# SCH_NFC-Card-Brianna_2024-10-25.net
KiCad netlist of a schematic drawn in EasyEDA
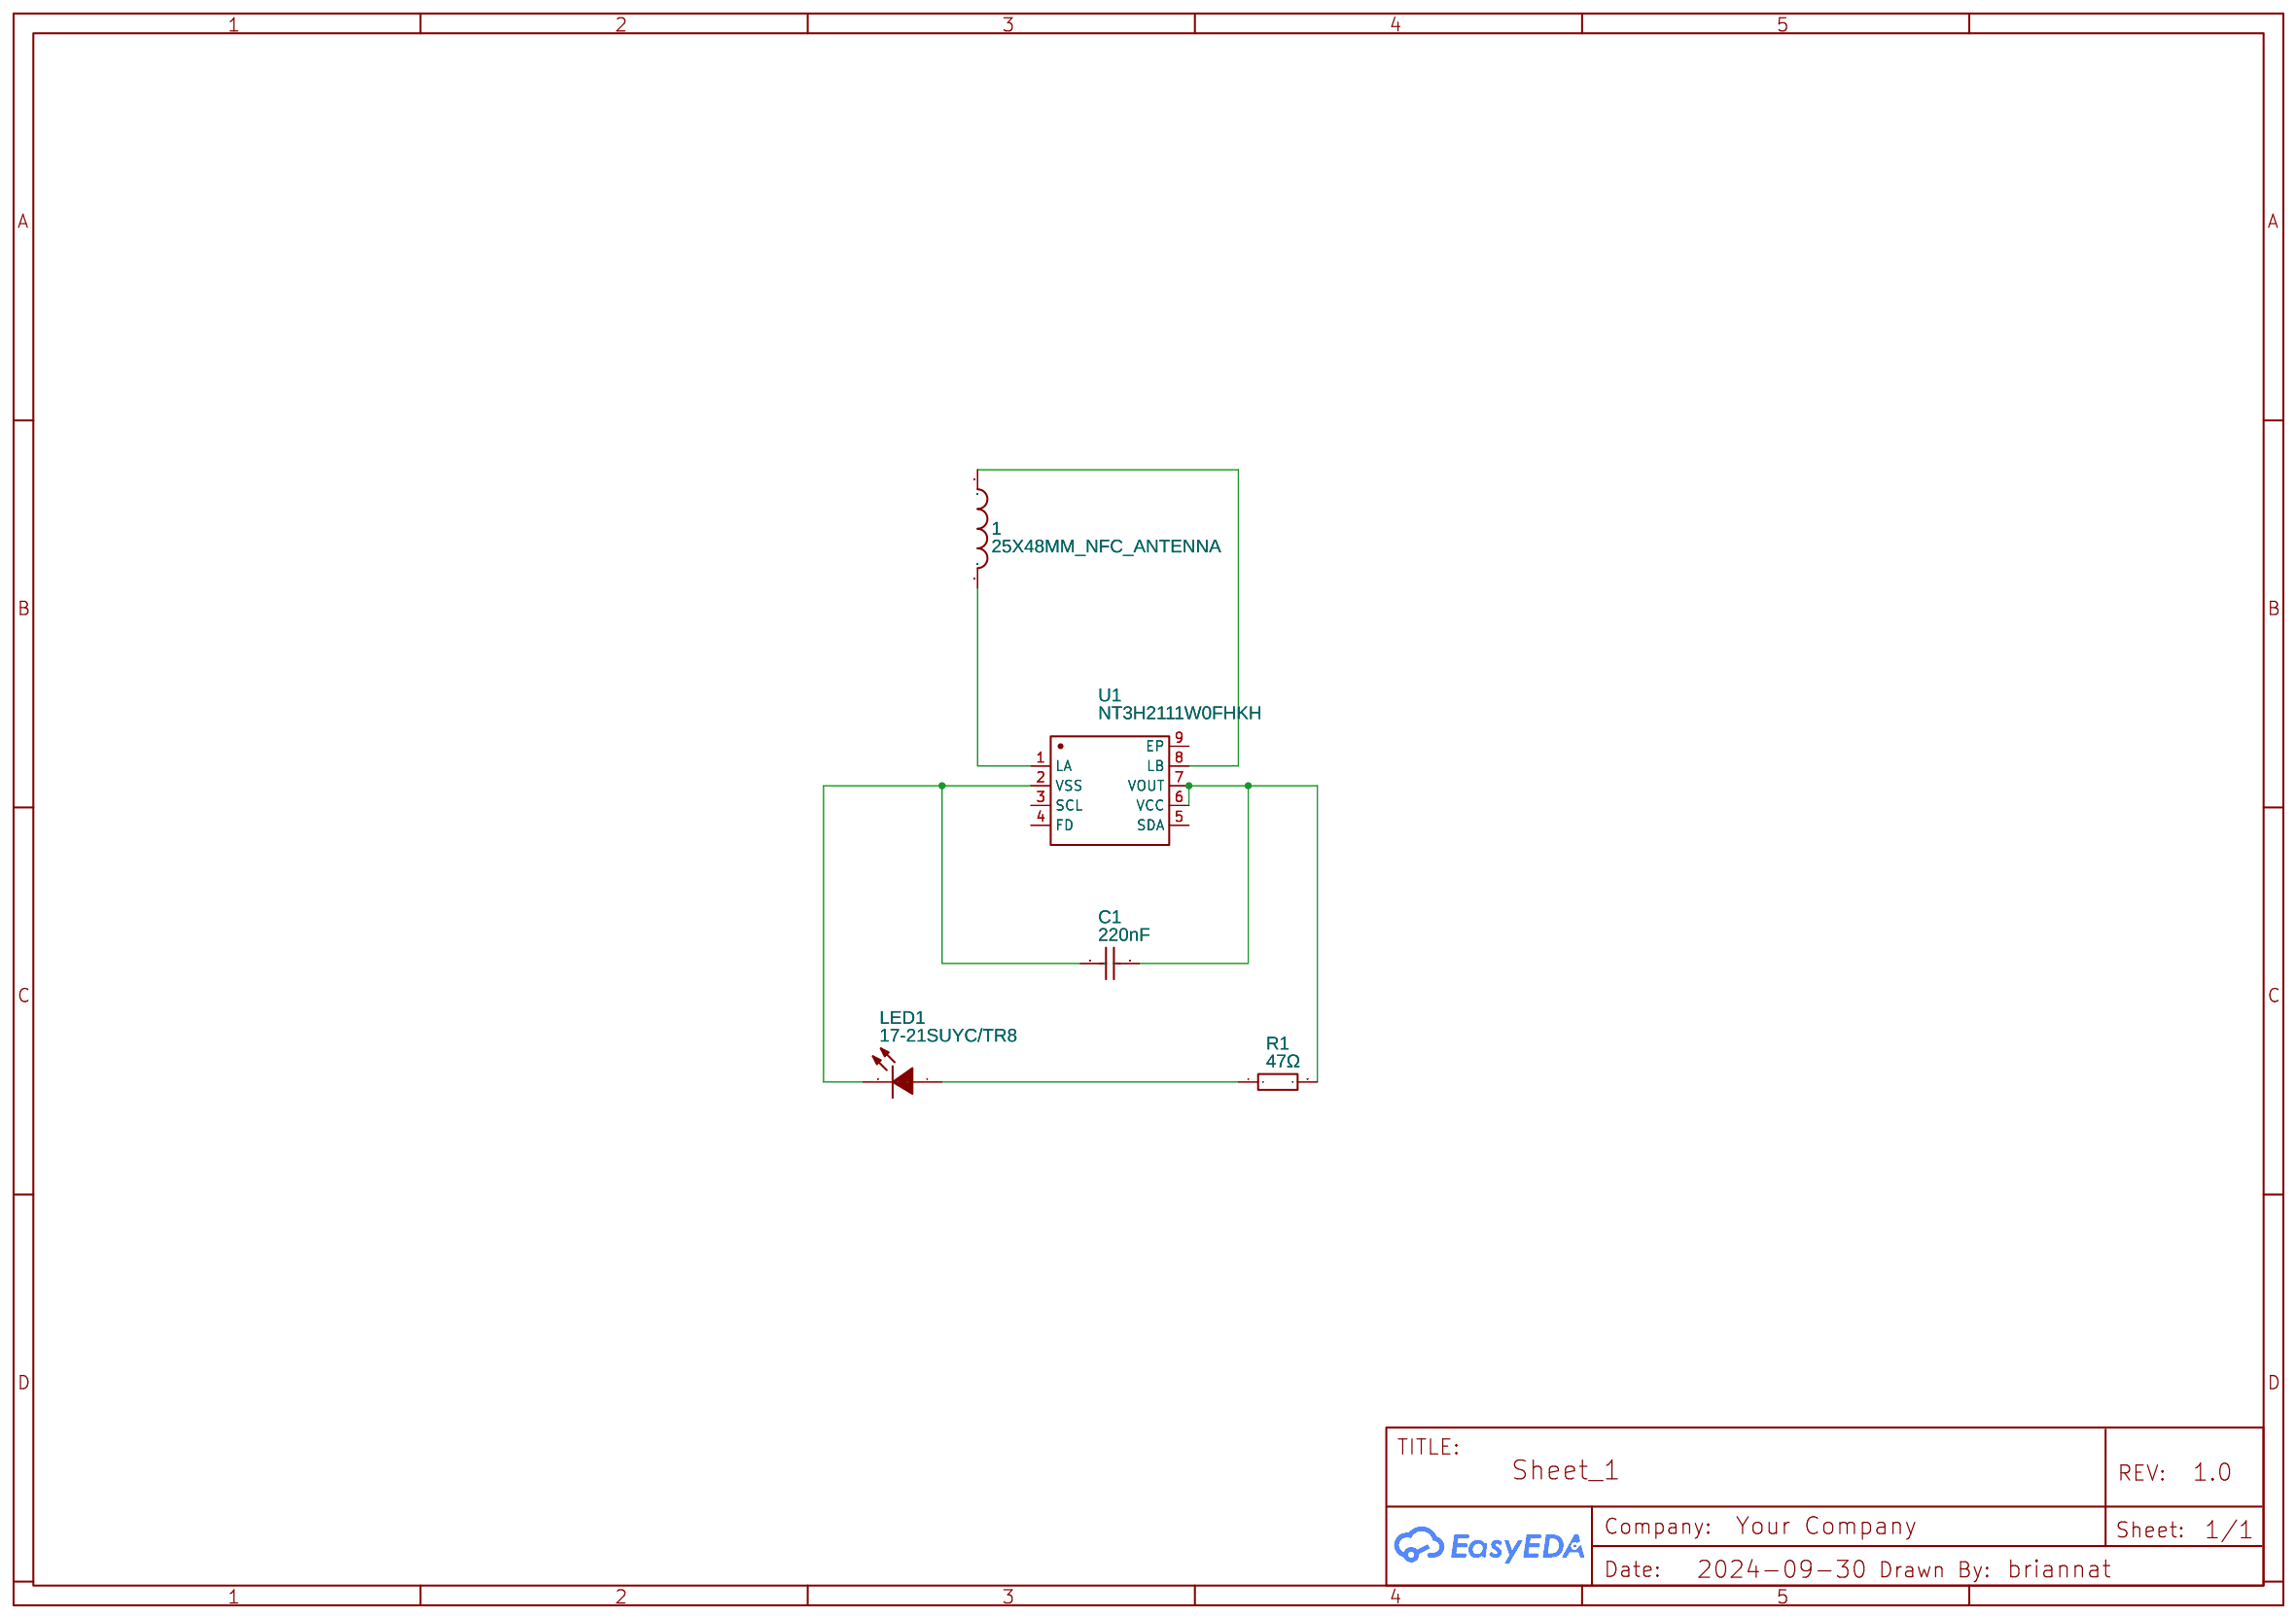
[diagram p0: schematic sheet]

(export (version "E")
  (design (tool "Eeschema 10.0.6"))
  (components
    (comp (ref "1") (value "25X48MM_NFC_ANTENNA") (libsource (lib "") (part "25X48MM_NFC_ANTENNA")))
    (comp (ref "C1")
      (value "220nF")
      (fields
        (field (name "Manufacturer Part") "CL10B224KA8NNNC")
        (field (name "Manufacturer") "SAMSUNG(三星)")
      )
      (libsource (lib "") (part "CL10B224KA8NNNC"))
    )
    (comp (ref "LED1")
      (value "17-21SUYC/TR8")
      (fields (field (name "Manufacturer Part") "KT-0805黄灯") (field (name "Manufacturer") "KENTO"))
      (libsource (lib "") (part "17-21SUYC/TR8"))
    )
    (comp (ref "R1")
      (value "47Ω")
      (fields
        (field (name "Manufacturer Part") "0603WAF470JT5E")
        (field (name "Manufacturer") "UNI-ROYAL(厚声)")
      )
      (libsource (lib "") (part "0603WAF470JT5E"))
    )
    (comp (ref "U1")
      (value "NT3H2111W0FHKH")
      (fields (field (name "Manufacturer") "NXP(恩智浦)"))
      (libsource (lib "") (part "NT3H2111W0FHKH"))
    )
  )
  (nets
    (net (code "1") (name "Net-(LED1-+)") (class "Default")
      (node (ref "LED1") (pin "1") (pinfunction "+_1") (pintype "unspecified"))
      (node (ref "R1") (pin "1") (pinfunction "1_1") (pintype "input"))
    )
    (net (code "2") (name "Net-(LED1--)") (class "Default")
      (node (ref "C1") (pin "1") (pinfunction "1_1") (pintype "input"))
      (node (ref "LED1") (pin "2") (pinfunction "-_2") (pintype "unspecified"))
      (node (ref "U1") (pin "2") (pinfunction "VSS_2") (pintype "unspecified"))
    )
    (net (code "3") (name "Net-(U1-LA)") (class "Default")
      (node (ref "1") (pin "P$2") (pinfunction "P$2_P$2") (pintype "bidirectional"))
      (node (ref "U1") (pin "1") (pinfunction "LA_1") (pintype "unspecified"))
    )
    (net (code "4") (name "Net-(U1-LB)") (class "Default")
      (node (ref "1") (pin "P$1") (pinfunction "P$1_P$1") (pintype "bidirectional"))
      (node (ref "U1") (pin "8") (pinfunction "LB_8") (pintype "unspecified"))
    )
    (net (code "5") (name "Net-(U1-VCC)") (class "Default")
      (node (ref "C1") (pin "2") (pinfunction "2_2") (pintype "input"))
      (node (ref "R1") (pin "2") (pinfunction "2_2") (pintype "input"))
      (node (ref "U1") (pin "6") (pinfunction "VCC_6") (pintype "unspecified"))
      (node (ref "U1") (pin "7") (pinfunction "VOUT_7") (pintype "unspecified"))
    )
    (net (code "6") (name "unconnected-(U1-EP-Pad9)") (class "Default")
      (node (ref "U1") (pin "9") (pinfunction "EP_9") (pintype "unspecified"))
    )
    (net (code "7") (name "unconnected-(U1-FD-Pad4)") (class "Default")
      (node (ref "U1") (pin "4") (pinfunction "FD_4") (pintype "unspecified"))
    )
    (net (code "8") (name "unconnected-(U1-SCL-Pad3)") (class "Default")
      (node (ref "U1") (pin "3") (pinfunction "SCL_3") (pintype "unspecified"))
    )
    (net (code "9") (name "unconnected-(U1-SDA-Pad5)") (class "Default")
      (node (ref "U1") (pin "5") (pinfunction "SDA_5") (pintype "unspecified"))
    )
  )
)
